# 2-Displays.net
KiCad netlist of a schematic drawn in EAGLE
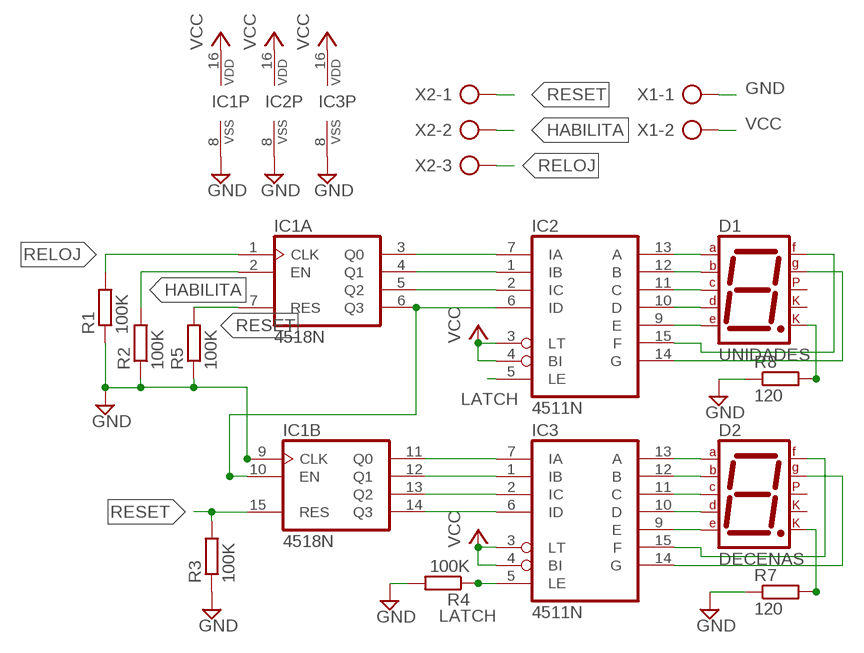
[diagram p0: schematic, sheet 1]

(export (version "E")
  (design (tool "Eeschema 10.0.6"))
  (components
    (comp (ref "D1")
      (value "UNIDADES")
      (footprint "eagle-import:7SEG-13")
      (libsource (lib "eagle-import") (part "7SEG-CK"))
    )
    (comp (ref "D2")
      (value "DECENAS")
      (footprint "eagle-import:7SEG-13")
      (libsource (lib "eagle-import") (part "7SEG-CK"))
    )
    (comp (ref "IC1")
      (value "4518N")
      (footprint "eagle-import:DIL16")
      (libsource (lib "eagle-import") (part "4518N"))
    )
    (comp (ref "IC2")
      (value "4511N")
      (footprint "eagle-import:DIL16")
      (libsource (lib "eagle-import") (part "4511N"))
    )
    (comp (ref "IC3")
      (value "4511N")
      (footprint "eagle-import:DIL16")
      (libsource (lib "eagle-import") (part "4511N"))
    )
    (comp (ref "R1")
      (value "100K")
      (footprint "eagle-import:0207_7")
      (libsource (lib "eagle-import") (part "R-EU_0207/7"))
    )
    (comp (ref "R2")
      (value "100K")
      (footprint "eagle-import:0207_7")
      (libsource (lib "eagle-import") (part "R-EU_0207/7"))
    )
    (comp (ref "R3")
      (value "100K")
      (footprint "eagle-import:0207_7")
      (libsource (lib "eagle-import") (part "R-EU_0207/7"))
    )
    (comp (ref "R4")
      (value "100K")
      (footprint "eagle-import:0207_7")
      (libsource (lib "eagle-import") (part "R-EU_0207/7"))
    )
    (comp (ref "R5")
      (value "100K")
      (footprint "eagle-import:0207_7")
      (libsource (lib "eagle-import") (part "R-EU_0207/7"))
    )
    (comp (ref "R7")
      (value "120")
      (footprint "eagle-import:0207_7")
      (libsource (lib "eagle-import") (part "R-EU_0207/7"))
    )
    (comp (ref "R8")
      (value "120")
      (footprint "eagle-import:0207_7")
      (libsource (lib "eagle-import") (part "R-EU_0207/7"))
    )
    (comp (ref "X1")
      (value "AK500/2-H")
      (footprint "eagle-import:AK500_2-H")
      (libsource (lib "eagle-import") (part "AK500/2-H"))
    )
    (comp (ref "X2")
      (value "AK500/3-H")
      (footprint "eagle-import:AK500_3-H")
      (libsource (lib "eagle-import") (part "AK500/3-H"))
    )
  )
  (nets
    (net (code "1") (name "/LATCH") (class "Default")
      (node (ref "IC2") (pin "5") (pinfunction "LE_5") (pintype "input"))
      (node (ref "IC3") (pin "5") (pinfunction "LE_5") (pintype "input"))
      (node (ref "R4") (pin "1") (pinfunction "1_1") (pintype "passive"))
    )
    (net (code "2") (name "GND") (class "Default")
      (node (ref "IC1") (pin "8") (pinfunction "VSS_8") (pintype "power_in"))
      (node (ref "IC1") (pin "9") (pinfunction "CLK_9") (pintype "input"))
      (node (ref "IC2") (pin "8") (pinfunction "VSS_8") (pintype "power_in"))
      (node (ref "IC3") (pin "8") (pinfunction "VSS_8") (pintype "power_in"))
      (node (ref "R1") (pin "1") (pinfunction "1_1") (pintype "passive"))
      (node (ref "R2") (pin "1") (pinfunction "1_1") (pintype "passive"))
      (node (ref "R3") (pin "1") (pinfunction "1_1") (pintype "passive"))
      (node (ref "R4") (pin "2") (pinfunction "2_2") (pintype "passive"))
      (node (ref "R5") (pin "1") (pinfunction "1_1") (pintype "passive"))
      (node (ref "R7") (pin "1") (pinfunction "1_1") (pintype "passive"))
      (node (ref "R8") (pin "1") (pinfunction "1_1") (pintype "passive"))
      (node (ref "X1") (pin "1") (pinfunction "KL_1") (pintype "passive"))
    )
    (net (code "3") (name "HABILITA") (class "Default")
      (node (ref "IC1") (pin "2") (pinfunction "EN_2") (pintype "input"))
      (node (ref "R2") (pin "2") (pinfunction "2_2") (pintype "passive"))
      (node (ref "X2") (pin "2") (pinfunction "KL_2") (pintype "passive"))
    )
    (net (code "4") (name "Net-(D1-A)") (class "Default")
      (node (ref "D1") (pin "7") (pinfunction "A_7") (pintype "passive"))
      (node (ref "IC2") (pin "13") (pinfunction "A_13") (pintype "output"))
    )
    (net (code "5") (name "Net-(D1-B)") (class "Default")
      (node (ref "D1") (pin "6") (pinfunction "B_6") (pintype "passive"))
      (node (ref "IC2") (pin "12") (pinfunction "B_12") (pintype "output"))
    )
    (net (code "6") (name "Net-(D1-C)") (class "Default")
      (node (ref "D1") (pin "4") (pinfunction "C_4") (pintype "passive"))
      (node (ref "IC2") (pin "11") (pinfunction "C_11") (pintype "output"))
    )
    (net (code "7") (name "Net-(D1-CK2)") (class "Default")
      (node (ref "D1") (pin "8") (pinfunction "CK2_8") (pintype "passive"))
      (node (ref "R8") (pin "2") (pinfunction "2_2") (pintype "passive"))
    )
    (net (code "8") (name "Net-(D1-D)") (class "Default")
      (node (ref "D1") (pin "2") (pinfunction "D_2") (pintype "passive"))
      (node (ref "IC2") (pin "10") (pinfunction "D_10") (pintype "output"))
    )
    (net (code "9") (name "Net-(D1-E)") (class "Default")
      (node (ref "D1") (pin "1") (pinfunction "E_1") (pintype "passive"))
      (node (ref "IC2") (pin "9") (pinfunction "E_9") (pintype "output"))
    )
    (net (code "10") (name "Net-(D1-F)") (class "Default")
      (node (ref "D1") (pin "9") (pinfunction "F_9") (pintype "passive"))
      (node (ref "IC2") (pin "15") (pinfunction "F_15") (pintype "output"))
    )
    (net (code "11") (name "Net-(D1-G)") (class "Default")
      (node (ref "D1") (pin "10") (pinfunction "G_10") (pintype "passive"))
      (node (ref "IC2") (pin "14") (pinfunction "G_14") (pintype "output"))
    )
    (net (code "12") (name "Net-(D2-A)") (class "Default")
      (node (ref "D2") (pin "7") (pinfunction "A_7") (pintype "passive"))
      (node (ref "IC3") (pin "13") (pinfunction "A_13") (pintype "output"))
    )
    (net (code "13") (name "Net-(D2-B)") (class "Default")
      (node (ref "D2") (pin "6") (pinfunction "B_6") (pintype "passive"))
      (node (ref "IC3") (pin "12") (pinfunction "B_12") (pintype "output"))
    )
    (net (code "14") (name "Net-(D2-C)") (class "Default")
      (node (ref "D2") (pin "4") (pinfunction "C_4") (pintype "passive"))
      (node (ref "IC3") (pin "11") (pinfunction "C_11") (pintype "output"))
    )
    (net (code "15") (name "Net-(D2-CK2)") (class "Default")
      (node (ref "D2") (pin "8") (pinfunction "CK2_8") (pintype "passive"))
      (node (ref "R7") (pin "2") (pinfunction "2_2") (pintype "passive"))
    )
    (net (code "16") (name "Net-(D2-D)") (class "Default")
      (node (ref "D2") (pin "2") (pinfunction "D_2") (pintype "passive"))
      (node (ref "IC3") (pin "10") (pinfunction "D_10") (pintype "output"))
    )
    (net (code "17") (name "Net-(D2-E)") (class "Default")
      (node (ref "D2") (pin "1") (pinfunction "E_1") (pintype "passive"))
      (node (ref "IC3") (pin "9") (pinfunction "E_9") (pintype "output"))
    )
    (net (code "18") (name "Net-(D2-F)") (class "Default")
      (node (ref "D2") (pin "9") (pinfunction "F_9") (pintype "passive"))
      (node (ref "IC3") (pin "15") (pinfunction "F_15") (pintype "output"))
    )
    (net (code "19") (name "Net-(D2-G)") (class "Default")
      (node (ref "D2") (pin "10") (pinfunction "G_10") (pintype "passive"))
      (node (ref "IC3") (pin "14") (pinfunction "G_14") (pintype "output"))
    )
    (net (code "20") (name "Net-(IC1A-Q0)") (class "Default")
      (node (ref "IC1") (pin "3") (pinfunction "Q0_3") (pintype "output"))
      (node (ref "IC2") (pin "7") (pinfunction "IA_7") (pintype "input"))
    )
    (net (code "21") (name "Net-(IC1A-Q1)") (class "Default")
      (node (ref "IC1") (pin "4") (pinfunction "Q1_4") (pintype "output"))
      (node (ref "IC2") (pin "1") (pinfunction "IB_1") (pintype "input"))
    )
    (net (code "22") (name "Net-(IC1A-Q2)") (class "Default")
      (node (ref "IC1") (pin "5") (pinfunction "Q2_5") (pintype "output"))
      (node (ref "IC2") (pin "2") (pinfunction "IC_2") (pintype "input"))
    )
    (net (code "23") (name "Net-(IC1A-Q3)") (class "Default")
      (node (ref "IC1") (pin "10") (pinfunction "EN_10") (pintype "input"))
      (node (ref "IC1") (pin "6") (pinfunction "Q3_6") (pintype "output"))
      (node (ref "IC2") (pin "6") (pinfunction "ID_6") (pintype "input"))
    )
    (net (code "24") (name "Net-(IC1B-Q0)") (class "Default")
      (node (ref "IC1") (pin "11") (pinfunction "Q0_11") (pintype "output"))
      (node (ref "IC3") (pin "7") (pinfunction "IA_7") (pintype "input"))
    )
    (net (code "25") (name "Net-(IC1B-Q1)") (class "Default")
      (node (ref "IC1") (pin "12") (pinfunction "Q1_12") (pintype "output"))
      (node (ref "IC3") (pin "1") (pinfunction "IB_1") (pintype "input"))
    )
    (net (code "26") (name "Net-(IC1B-Q2)") (class "Default")
      (node (ref "IC1") (pin "13") (pinfunction "Q2_13") (pintype "output"))
      (node (ref "IC3") (pin "2") (pinfunction "IC_2") (pintype "input"))
    )
    (net (code "27") (name "Net-(IC1B-Q3)") (class "Default")
      (node (ref "IC1") (pin "14") (pinfunction "Q3_14") (pintype "output"))
      (node (ref "IC3") (pin "6") (pinfunction "ID_6") (pintype "input"))
    )
    (net (code "28") (name "RELOJ") (class "Default")
      (node (ref "IC1") (pin "1") (pinfunction "CLK_1") (pintype "input"))
      (node (ref "R1") (pin "2") (pinfunction "2_2") (pintype "passive"))
      (node (ref "X2") (pin "3") (pinfunction "KL_3") (pintype "passive"))
    )
    (net (code "29") (name "RESET") (class "Default")
      (node (ref "IC1") (pin "15") (pinfunction "RES_15") (pintype "input"))
      (node (ref "IC1") (pin "7") (pinfunction "RES_7") (pintype "input"))
      (node (ref "R3") (pin "2") (pinfunction "2_2") (pintype "passive"))
      (node (ref "R5") (pin "2") (pinfunction "2_2") (pintype "passive"))
      (node (ref "X2") (pin "1") (pinfunction "KL_1") (pintype "passive"))
    )
    (net (code "30") (name "VCC") (class "Default")
      (node (ref "IC1") (pin "16") (pinfunction "VDD_16") (pintype "power_in"))
      (node (ref "IC2") (pin "16") (pinfunction "VDD_16") (pintype "power_in"))
      (node (ref "IC2") (pin "3") (pinfunction "LT_3") (pintype "input"))
      (node (ref "IC2") (pin "4") (pinfunction "BI_4") (pintype "input"))
      (node (ref "IC3") (pin "16") (pinfunction "VDD_16") (pintype "power_in"))
      (node (ref "IC3") (pin "3") (pinfunction "LT_3") (pintype "input"))
      (node (ref "IC3") (pin "4") (pinfunction "BI_4") (pintype "input"))
      (node (ref "X1") (pin "2") (pinfunction "KL_2") (pintype "passive"))
    )
    (net (code "31") (name "unconnected-(D1-CK1-Pad3)") (class "Default")
      (node (ref "D1") (pin "3") (pinfunction "CK1_3") (pintype "passive"))
    )
    (net (code "32") (name "unconnected-(D1-DP-Pad5)") (class "Default")
      (node (ref "D1") (pin "5") (pinfunction "DP_5") (pintype "passive"))
    )
    (net (code "33") (name "unconnected-(D2-CK1-Pad3)") (class "Default")
      (node (ref "D2") (pin "3") (pinfunction "CK1_3") (pintype "passive"))
    )
    (net (code "34") (name "unconnected-(D2-DP-Pad5)") (class "Default")
      (node (ref "D2") (pin "5") (pinfunction "DP_5") (pintype "passive"))
    )
  )
)
